# ESP-TemperatureSensor.net
KiCad netlist of a schematic drawn in EAGLE
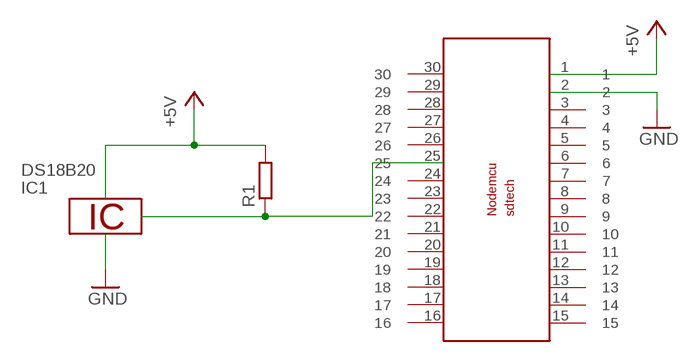
[diagram p0: schematic, sheet 1]

(export (version "E")
  (design (tool "Eeschema 10.0.6"))
  (components
    (comp (ref "IC1")
      (value "DS18B20")
      (footprint "eagle-import:TO92-")
      (libsource (lib "eagle-import") (part "DS18B20"))
    )
    (comp (ref "R1")
      (value "R-EU_0204/2V")
      (footprint "eagle-import:0204V")
      (libsource (lib "eagle-import") (part "R-EU_0204/2V"))
    )
    (comp (ref "U$1")
      (value "NODEMCUESP8266")
      (footprint "eagle-import:NODEMCUESP8266")
      (libsource (lib "eagle-import") (part "NODEMCUESP8266"))
    )
  )
  (nets
    (net (code "1") (name "+5V") (class "Default")
      (node (ref "R1") (pin "2") (pinfunction "2_2") (pintype "passive"))
      (node (ref "U$1") (pin "1") (pinfunction "1_1") (pintype "bidirectional"))
    )
    (net (code "2") (name "GND") (class "Default")
      (node (ref "U$1") (pin "2") (pinfunction "2_2") (pintype "bidirectional"))
    )
    (net (code "3") (name "Net-(R1-Pad1)") (class "Default")
      (node (ref "R1") (pin "1") (pinfunction "1_1") (pintype "passive"))
      (node (ref "U$1") (pin "25") (pinfunction "25_25") (pintype "bidirectional"))
    )
    (net (code "4") (name "unconnected-(U$1-Pad3)") (class "Default")
      (node (ref "U$1") (pin "3") (pinfunction "3_3") (pintype "bidirectional"))
    )
    (net (code "5") (name "unconnected-(U$1-Pad4)") (class "Default")
      (node (ref "U$1") (pin "4") (pinfunction "4_4") (pintype "bidirectional"))
    )
    (net (code "6") (name "unconnected-(U$1-Pad5)") (class "Default")
      (node (ref "U$1") (pin "5") (pinfunction "5_5") (pintype "bidirectional"))
    )
    (net (code "7") (name "unconnected-(U$1-Pad6)") (class "Default")
      (node (ref "U$1") (pin "6") (pinfunction "6_6") (pintype "bidirectional"))
    )
    (net (code "8") (name "unconnected-(U$1-Pad7)") (class "Default")
      (node (ref "U$1") (pin "7") (pinfunction "7_7") (pintype "bidirectional"))
    )
    (net (code "9") (name "unconnected-(U$1-Pad8)") (class "Default")
      (node (ref "U$1") (pin "8") (pinfunction "8_8") (pintype "bidirectional"))
    )
    (net (code "10") (name "unconnected-(U$1-Pad9)") (class "Default")
      (node (ref "U$1") (pin "9") (pinfunction "9_9") (pintype "bidirectional"))
    )
    (net (code "11") (name "unconnected-(U$1-Pad10)") (class "Default")
      (node (ref "U$1") (pin "10") (pinfunction "10_10") (pintype "bidirectional"))
    )
    (net (code "12") (name "unconnected-(U$1-Pad11)") (class "Default")
      (node (ref "U$1") (pin "11") (pinfunction "11_11") (pintype "bidirectional"))
    )
    (net (code "13") (name "unconnected-(U$1-Pad12)") (class "Default")
      (node (ref "U$1") (pin "12") (pinfunction "12_12") (pintype "bidirectional"))
    )
    (net (code "14") (name "unconnected-(U$1-Pad13)") (class "Default")
      (node (ref "U$1") (pin "13") (pinfunction "13_13") (pintype "bidirectional"))
    )
    (net (code "15") (name "unconnected-(U$1-Pad14)") (class "Default")
      (node (ref "U$1") (pin "14") (pinfunction "14_14") (pintype "bidirectional"))
    )
    (net (code "16") (name "unconnected-(U$1-Pad15)") (class "Default")
      (node (ref "U$1") (pin "15") (pinfunction "15_15") (pintype "bidirectional"))
    )
    (net (code "17") (name "unconnected-(U$1-Pad16)") (class "Default")
      (node (ref "U$1") (pin "16") (pinfunction "16_16") (pintype "bidirectional"))
    )
    (net (code "18") (name "unconnected-(U$1-Pad17)") (class "Default")
      (node (ref "U$1") (pin "17") (pinfunction "17_17") (pintype "bidirectional"))
    )
    (net (code "19") (name "unconnected-(U$1-Pad18)") (class "Default")
      (node (ref "U$1") (pin "18") (pinfunction "18_18") (pintype "bidirectional"))
    )
    (net (code "20") (name "unconnected-(U$1-Pad19)") (class "Default")
      (node (ref "U$1") (pin "19") (pinfunction "19_19") (pintype "bidirectional"))
    )
    (net (code "21") (name "unconnected-(U$1-Pad20)") (class "Default")
      (node (ref "U$1") (pin "20") (pinfunction "20_20") (pintype "bidirectional"))
    )
    (net (code "22") (name "unconnected-(U$1-Pad21)") (class "Default")
      (node (ref "U$1") (pin "21") (pinfunction "21_21") (pintype "bidirectional"))
    )
    (net (code "23") (name "unconnected-(U$1-Pad22)") (class "Default")
      (node (ref "U$1") (pin "22") (pinfunction "22_22") (pintype "bidirectional"))
    )
    (net (code "24") (name "unconnected-(U$1-Pad23)") (class "Default")
      (node (ref "U$1") (pin "23") (pinfunction "23_23") (pintype "bidirectional"))
    )
    (net (code "25") (name "unconnected-(U$1-Pad24)") (class "Default")
      (node (ref "U$1") (pin "24") (pinfunction "24_24") (pintype "bidirectional"))
    )
    (net (code "26") (name "unconnected-(U$1-Pad26)") (class "Default")
      (node (ref "U$1") (pin "26") (pinfunction "26_26") (pintype "bidirectional"))
    )
    (net (code "27") (name "unconnected-(U$1-Pad27)") (class "Default")
      (node (ref "U$1") (pin "27") (pinfunction "27_27") (pintype "bidirectional"))
    )
    (net (code "28") (name "unconnected-(U$1-Pad28)") (class "Default")
      (node (ref "U$1") (pin "28") (pinfunction "28_28") (pintype "bidirectional"))
    )
    (net (code "29") (name "unconnected-(U$1-Pad29)") (class "Default")
      (node (ref "U$1") (pin "29") (pinfunction "29_29") (pintype "bidirectional"))
    )
    (net (code "30") (name "unconnected-(U$1-Pad30)") (class "Default")
      (node (ref "U$1") (pin "30") (pinfunction "30_30") (pintype "bidirectional"))
    )
  )
)
